# pic_blk.net
KiCad netlist of a schematic drawn in Altium Designer
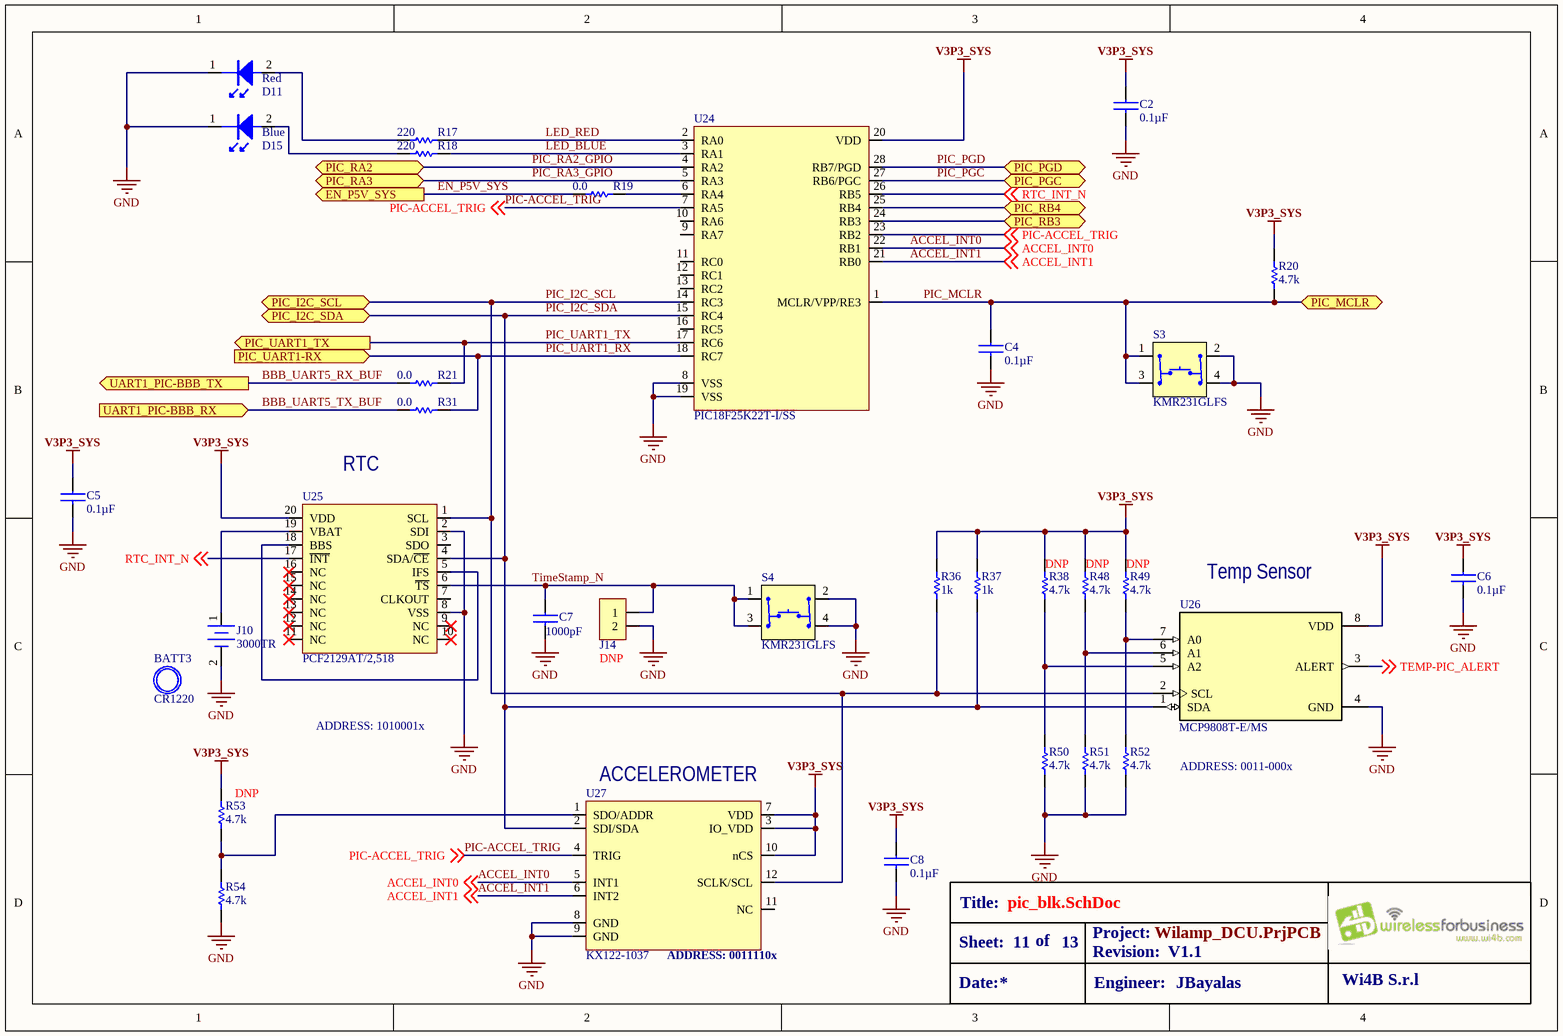
[diagram p0: pic_blk.SchDoc]

(export (version "E")
  (design (tool "Eeschema 10.0.6"))
  (components
    (comp (ref "BATT3")
      (value "CR1220")
      (description "Coin Cell Battery 35mAh 12.5mm")
      (fields (field (name "MPN") "CR1220"))
      (libsource (lib "Miscellaneous") (part "CR1220"))
    )
    (comp (ref "C2")
      (value "0.1µF")
      (footprint "C0402")
      (description "CAP CER 0.1UF 16V X7R 0402")
      (fields (field (name "MPN") "CL05B104KO3LNNC"))
      (libsource (lib "Capacitor") (part "CL05B104KO3LNNC"))
    )
    (comp (ref "C4")
      (value "0.1µF")
      (footprint "C0402")
      (description "CAP CER 0.1UF 16V X7R 0402")
      (fields (field (name "MPN") "CL05B104KO3LNNC"))
      (libsource (lib "Capacitor") (part "CL05B104KO3LNNC"))
    )
    (comp (ref "C5")
      (value "0.1µF")
      (footprint "C0402")
      (description "CAP CER 0.1UF 16V X7R 0402")
      (fields (field (name "MPN") "CL05B104KO3LNNC"))
      (libsource (lib "Capacitor") (part "CL05B104KO3LNNC"))
    )
    (comp (ref "C6")
      (value "0.1µF")
      (footprint "C0402")
      (description "CAP CER 0.1UF 16V X7R 0402")
      (fields (field (name "MPN") "CL05B104KO3LNNC"))
      (libsource (lib "Capacitor") (part "CL05B104KO3LNNC"))
    )
    (comp (ref "C7")
      (value "1000pF")
      (footprint "C0402")
      (description "CAP CER 1000PF 50V X7R 0402")
      (fields (field (name "MPN") "GRM155R71H102KA01D"))
      (libsource (lib "Capacitor") (part "GRM155R71H102KA01D"))
    )
    (comp (ref "C8")
      (value "0.1µF")
      (footprint "C0402")
      (description "CAP CER 0.1UF 16V X7R 0402")
      (fields (field (name "MPN") "CL05B104KO3LNNC"))
      (libsource (lib "Capacitor") (part "CL05B104KO3LNNC"))
    )
    (comp (ref "D11")
      (value "Red")
      (footprint "LED0402(RED)")
      (description "LED RED 0402 SMD")
      (fields (field (name "MPN") "LNJ247W82RA"))
      (libsource (lib "Diode") (part "LNJ247W82RA"))
    )
    (comp (ref "D15")
      (value "Blue")
      (footprint "LED0402(BLUE)")
      (description "LED BLUE 0402 SMD")
      (fields (field (name "MPN") "VLMB1500-GS08"))
      (libsource (lib "Diode") (part "VLMB1500-GS08"))
    )
    (comp (ref "J10")
      (value "3000TR")
      (footprint "3000TR")
      (description "Coin Cell Battery Holders SM COIN CELL B/H")
      (libsource (lib "Connector") (part "3000TR"))
    )
    (comp (ref "J14")
      (value "*")
      (footprint "2pin 5mm Pitch")
      (fields (field (name "LOAD") "DNP"))
      (libsource (lib "Miscellaneous") (part "2PIN Signal 5mm Pitch"))
    )
    (comp (ref "R17")
      (value "220")
      (footprint "R0402")
      (description "RES SMD 220 OHM 5% 1/16W 0402")
      (fields (field (name "MPN") "RC0402JR-07220RL"))
      (libsource (lib "Res") (part "RC0402JR-07220RL"))
    )
    (comp (ref "R18")
      (value "220")
      (footprint "R0402")
      (description "RES SMD 220 OHM 5% 1/16W 0402")
      (fields (field (name "MPN") "RC0402JR-07220RL"))
      (libsource (lib "Res") (part "RC0402JR-07220RL"))
    )
    (comp (ref "R19")
      (value "0.0")
      (footprint "R0402")
      (description "RES SMD 0.0OHM JUMPER 1/16W 0402")
      (fields (field (name "MPN") "CRCW04020000Z0ED"))
      (libsource (lib "Res") (part "CRCW04020000Z0ED"))
    )
    (comp (ref "R20")
      (value "4.7k")
      (footprint "R0603")
      (description "RES SMD 4.7K OHM 0.1% 1/10W 0603")
      (fields (field (name "MPN") "ERA-3AEB472V"))
      (libsource (lib "Res") (part "ERA-3AEB472V"))
    )
    (comp (ref "R21")
      (value "0.0")
      (footprint "R0402")
      (description "RES SMD 0.0OHM JUMPER 1/16W 0402")
      (fields (field (name "MPN") "CRCW04020000Z0ED"))
      (libsource (lib "Res") (part "CRCW04020000Z0ED"))
    )
    (comp (ref "R31")
      (value "0.0")
      (footprint "R0402")
      (description "RES SMD 0.0OHM JUMPER 1/16W 0402")
      (fields (field (name "MPN") "CRCW04020000Z0ED"))
      (libsource (lib "Res") (part "CRCW04020000Z0ED"))
    )
    (comp (ref "R36")
      (value "1k")
      (footprint "R0402")
      (description "RES SMD 1K OHM 1% 1/10W 0402")
      (fields (field (name "MPN") "MCS04020C1001FE000"))
      (libsource (lib "Res") (part "MCS04020C1001FE000"))
    )
    (comp (ref "R37")
      (value "1k")
      (footprint "R0402")
      (description "RES SMD 1K OHM 1% 1/10W 0402")
      (fields (field (name "MPN") "MCS04020C1001FE000"))
      (libsource (lib "Res") (part "MCS04020C1001FE000"))
    )
    (comp (ref "R38")
      (value "4.7k")
      (footprint "R0402")
      (description "RES SMD 4.7K OHM 5% 1/16W 0402")
      (fields (field (name "MPN") "RC0402JR-074K7L") (field (name "LOAD") "DNP"))
      (libsource (lib "Res") (part "RC0402JR-074K7L"))
    )
    (comp (ref "R48")
      (value "4.7k")
      (footprint "R0402")
      (description "RES SMD 4.7K OHM 5% 1/16W 0402")
      (fields (field (name "MPN") "RC0402JR-074K7L") (field (name "LOAD") "DNP"))
      (libsource (lib "Res") (part "RC0402JR-074K7L"))
    )
    (comp (ref "R49")
      (value "4.7k")
      (footprint "R0402")
      (description "RES SMD 4.7K OHM 5% 1/16W 0402")
      (fields (field (name "MPN") "RC0402JR-074K7L") (field (name "LOAD") "DNP"))
      (libsource (lib "Res") (part "RC0402JR-074K7L"))
    )
    (comp (ref "R50")
      (value "4.7k")
      (footprint "R0402")
      (description "RES SMD 4.7K OHM 5% 1/16W 0402")
      (fields (field (name "MPN") "RC0402JR-074K7L"))
      (libsource (lib "Res") (part "RC0402JR-074K7L"))
    )
    (comp (ref "R51")
      (value "4.7k")
      (footprint "R0402")
      (description "RES SMD 4.7K OHM 5% 1/16W 0402")
      (fields (field (name "MPN") "RC0402JR-074K7L"))
      (libsource (lib "Res") (part "RC0402JR-074K7L"))
    )
    (comp (ref "R52")
      (value "4.7k")
      (footprint "R0402")
      (description "RES SMD 4.7K OHM 5% 1/16W 0402")
      (fields (field (name "MPN") "RC0402JR-074K7L"))
      (libsource (lib "Res") (part "RC0402JR-074K7L"))
    )
    (comp (ref "R53")
      (value "4.7k")
      (footprint "R0402")
      (description "RES SMD 4.7K OHM 5% 1/16W 0402")
      (fields (field (name "MPN") "RC0402JR-074K7L") (field (name "LOAD") "DNP"))
      (libsource (lib "Res") (part "RC0402JR-074K7L"))
    )
    (comp (ref "R54")
      (value "4.7k")
      (footprint "R0402")
      (description "RES SMD 4.7K OHM 5% 1/16W 0402")
      (fields (field (name "MPN") "RC0402JR-074K7L"))
      (libsource (lib "Res") (part "RC0402JR-074K7L"))
    )
    (comp (ref "S3")
      (value "*")
      (footprint "KMR231G ULC LFS")
      (description "SWITCH TACTILE SPST-NO 0.05A 32V")
      (fields (field (name "MPN") "KMR231GLFS"))
      (libsource (lib "Switch") (part "KMR231GLFS"))
    )
    (comp (ref "S4")
      (value "*")
      (footprint "KMR231G ULC LFS")
      (description "SWITCH TACTILE SPST-NO 0.05A 32V")
      (fields (field (name "MPN") "KMR231GLFS"))
      (libsource (lib "Switch") (part "KMR231GLFS"))
    )
    (comp (ref "U24")
      (value "PIC18F25K22T-I/SS")
      (footprint "SSOP-28 (PIC)")
      (description "MCU 8BIT 32KB FLASH 28SSOP")
      (libsource (lib "IC") (part "PIC18F25K22T-I/SS"))
    )
    (comp (ref "U25")
      (value "PCF2129AT/2,518")
      (footprint "SOIC-20")
      (description "IC RTC /CALENDAR TCXO QTZ 20SOIC")
      (libsource (lib "IC") (part "PCF2129AT/2,518"))
    )
    (comp (ref "U26")
      (value "MCP9808T-E/MS")
      (footprint "SOP65P490X110-8N")
      (description "MCP9808 Series 3.6 V Memory Module Digital Temperature Sensor SMT - MSOP-8")
      (libsource (lib "SnapEDA") (part "MCP9808T-E/MS"))
    )
    (comp (ref "U27")
      (value "*")
      (footprint "KX122-1037")
      (description "ACCELEROMETER 2-8G I2C/SPI 12LGA")
      (fields (field (name "MPN") "KX122-1037"))
      (libsource (lib "IC") (part "KX122-1037"))
    )
  )
  (nets
    (net (code "1") (name "/BBB_UART5_RX_BUF") (class "Default")
      (node (ref "R21") (pin "2") (pinfunction "2_2") (pintype "passive"))
    )
    (net (code "2") (name "/BBB_UART5_TX_BUF") (class "Default")
      (node (ref "R31") (pin "2") (pinfunction "2_2") (pintype "passive"))
    )
    (net (code "3") (name "/EN_P5V_SYS") (class "Default")
      (node (ref "R19") (pin "2") (pinfunction "2_2") (pintype "passive"))
    )
    (net (code "4") (name "/LED_BLUE") (class "Default")
      (node (ref "R18") (pin "2") (pinfunction "2_2") (pintype "passive"))
      (node (ref "U24") (pin "3") (pinfunction "RA1_3") (pintype "passive"))
    )
    (net (code "5") (name "/LED_RED") (class "Default")
      (node (ref "R17") (pin "2") (pinfunction "2_2") (pintype "passive"))
      (node (ref "U24") (pin "2") (pinfunction "RA0_2") (pintype "passive"))
    )
    (net (code "6") (name "/PIC_I2C_SCL") (class "Default")
      (node (ref "R36") (pin "1") (pinfunction "1_1") (pintype "passive"))
      (node (ref "U24") (pin "14") (pinfunction "RC3_14") (pintype "passive"))
      (node (ref "U25") (pin "1") (pinfunction "SCL_1") (pintype "passive"))
      (node (ref "U26") (pin "2") (pinfunction "SCL_2") (pintype "input"))
      (node (ref "U27") (pin "12") (pinfunction "SCLK/SCL_12") (pintype "passive"))
    )
    (net (code "7") (name "/PIC_I2C_SDA") (class "Default")
      (node (ref "R37") (pin "1") (pinfunction "1_1") (pintype "passive"))
      (node (ref "U24") (pin "15") (pinfunction "RC4_15") (pintype "passive"))
      (node (ref "U25") (pin "4") (pinfunction "SDA/~{CE}_4") (pintype "passive"))
      (node (ref "U26") (pin "1") (pinfunction "SDA_1") (pintype "bidirectional"))
      (node (ref "U27") (pin "2") (pinfunction "SDI/SDA_2") (pintype "passive"))
    )
    (net (code "8") (name "/PIC_MCLR") (class "Default")
      (node (ref "C4") (pin "1") (pinfunction "1_1") (pintype "passive"))
      (node (ref "R20") (pin "1") (pinfunction "1_1") (pintype "passive"))
      (node (ref "S3") (pin "1") (pinfunction "1_1") (pintype "passive"))
      (node (ref "S3") (pin "3") (pinfunction "3_3") (pintype "passive"))
      (node (ref "U24") (pin "1") (pinfunction "MCLR/VPP/RE3_1") (pintype "passive"))
    )
    (net (code "9") (name "/PIC_PGC") (class "Default")
      (node (ref "U24") (pin "27") (pinfunction "RB6/PGC_27") (pintype "passive"))
    )
    (net (code "10") (name "/PIC_PGD") (class "Default")
      (node (ref "U24") (pin "28") (pinfunction "RB7/PGD_28") (pintype "passive"))
    )
    (net (code "11") (name "/PIC_RA2_GPIO") (class "Default")
      (node (ref "U24") (pin "4") (pinfunction "RA2_4") (pintype "passive"))
    )
    (net (code "12") (name "/PIC_RA3_GPIO") (class "Default")
      (node (ref "U24") (pin "5") (pinfunction "RA3_5") (pintype "passive"))
    )
    (net (code "13") (name "/PIC_RB3") (class "Default")
      (node (ref "U24") (pin "24") (pinfunction "RB3_24") (pintype "passive"))
    )
    (net (code "14") (name "/PIC_RB4") (class "Default")
      (node (ref "U24") (pin "25") (pinfunction "RB4_25") (pintype "passive"))
    )
    (net (code "15") (name "/PIC_UART1_RX") (class "Default")
      (node (ref "R31") (pin "1") (pinfunction "1_1") (pintype "passive"))
      (node (ref "U24") (pin "18") (pinfunction "RC7_18") (pintype "passive"))
    )
    (net (code "16") (name "/PIC_UART1_TX") (class "Default")
      (node (ref "R21") (pin "1") (pinfunction "1_1") (pintype "passive"))
      (node (ref "U24") (pin "17") (pinfunction "RC6_17") (pintype "passive"))
    )
    (net (code "17") (name "/TimeStamp_N") (class "Default")
      (node (ref "C7") (pin "1") (pinfunction "1_1") (pintype "passive"))
      (node (ref "J14") (pin "1") (pinfunction "1_1") (pintype "passive"))
      (node (ref "S4") (pin "1") (pinfunction "1_1") (pintype "passive"))
      (node (ref "S4") (pin "3") (pinfunction "3_3") (pintype "passive"))
      (node (ref "U25") (pin "6") (pinfunction "~{TS}_6") (pintype "passive"))
    )
    (net (code "18") (name "ACCEL_INT0") (class "Default")
      (node (ref "U24") (pin "22") (pinfunction "RB1_22") (pintype "passive"))
      (node (ref "U27") (pin "5") (pinfunction "INT1_5") (pintype "passive"))
    )
    (net (code "19") (name "ACCEL_INT1") (class "Default")
      (node (ref "U24") (pin "21") (pinfunction "RB0_21") (pintype "passive"))
      (node (ref "U27") (pin "6") (pinfunction "INT2_6") (pintype "passive"))
    )
    (net (code "20") (name "GND") (class "Default")
      (node (ref "C2") (pin "2") (pinfunction "2_2") (pintype "passive"))
      (node (ref "C4") (pin "2") (pinfunction "2_2") (pintype "passive"))
      (node (ref "C5") (pin "2") (pinfunction "2_2") (pintype "passive"))
      (node (ref "C6") (pin "2") (pinfunction "2_2") (pintype "passive"))
      (node (ref "C7") (pin "2") (pinfunction "2_2") (pintype "passive"))
      (node (ref "C8") (pin "2") (pinfunction "2_2") (pintype "passive"))
      (node (ref "D11") (pin "1") (pinfunction "1_1") (pintype "passive"))
      (node (ref "D15") (pin "1") (pinfunction "1_1") (pintype "passive"))
      (node (ref "J10") (pin "2") (pinfunction "-_2") (pintype "passive"))
      (node (ref "J14") (pin "2") (pinfunction "2_2") (pintype "passive"))
      (node (ref "R50") (pin "1") (pinfunction "1_1") (pintype "passive"))
      (node (ref "R51") (pin "1") (pinfunction "1_1") (pintype "passive"))
      (node (ref "R52") (pin "1") (pinfunction "1_1") (pintype "passive"))
      (node (ref "R54") (pin "1") (pinfunction "1_1") (pintype "passive"))
      (node (ref "S3") (pin "2") (pinfunction "2_2") (pintype "passive"))
      (node (ref "S3") (pin "4") (pinfunction "4_4") (pintype "passive"))
      (node (ref "S4") (pin "2") (pinfunction "2_2") (pintype "passive"))
      (node (ref "S4") (pin "4") (pinfunction "4_4") (pintype "passive"))
      (node (ref "U24") (pin "19") (pinfunction "VSS_19") (pintype "passive"))
      (node (ref "U24") (pin "8") (pinfunction "VSS_8") (pintype "passive"))
      (node (ref "U25") (pin "2") (pinfunction "SDI_2") (pintype "passive"))
      (node (ref "U25") (pin "8") (pinfunction "VSS_8") (pintype "passive"))
      (node (ref "U26") (pin "4") (pinfunction "GND_4") (pintype "power_in"))
      (node (ref "U27") (pin "8") (pinfunction "GND_8") (pintype "passive"))
      (node (ref "U27") (pin "9") (pinfunction "GND_9") (pintype "passive"))
    )
    (net (code "21") (name "Net-(D11-Pad2)") (class "Default")
      (node (ref "D11") (pin "2") (pinfunction "2_2") (pintype "passive"))
      (node (ref "R17") (pin "1") (pinfunction "1_1") (pintype "passive"))
    )
    (net (code "22") (name "Net-(D15-Pad2)") (class "Default")
      (node (ref "D15") (pin "2") (pinfunction "2_2") (pintype "passive"))
      (node (ref "R18") (pin "1") (pinfunction "1_1") (pintype "passive"))
    )
    (net (code "23") (name "Net-(J10-+)") (class "Default")
      (node (ref "J10") (pin "1") (pinfunction "+_1") (pintype "passive"))
      (node (ref "U25") (pin "19") (pinfunction "VBAT_19") (pintype "passive"))
    )
    (net (code "24") (name "Net-(U24-RA4)") (class "Default")
      (node (ref "R19") (pin "1") (pinfunction "1_1") (pintype "passive"))
      (node (ref "U24") (pin "6") (pinfunction "RA4_6") (pintype "passive"))
    )
    (net (code "25") (name "Net-(U25-BBS)") (class "Default")
      (node (ref "U25") (pin "18") (pinfunction "BBS_18") (pintype "passive"))
      (node (ref "U25") (pin "5") (pinfunction "IFS_5") (pintype "passive"))
    )
    (net (code "26") (name "Net-(U26-A0)") (class "Default")
      (node (ref "R49") (pin "1") (pinfunction "1_1") (pintype "passive"))
      (node (ref "R52") (pin "2") (pinfunction "2_2") (pintype "passive"))
      (node (ref "U26") (pin "7") (pinfunction "A0_7") (pintype "input"))
    )
    (net (code "27") (name "Net-(U26-A1)") (class "Default")
      (node (ref "R48") (pin "1") (pinfunction "1_1") (pintype "passive"))
      (node (ref "R51") (pin "2") (pinfunction "2_2") (pintype "passive"))
      (node (ref "U26") (pin "6") (pinfunction "A1_6") (pintype "input"))
    )
    (net (code "28") (name "Net-(U26-A2)") (class "Default")
      (node (ref "R38") (pin "1") (pinfunction "1_1") (pintype "passive"))
      (node (ref "R50") (pin "2") (pinfunction "2_2") (pintype "passive"))
      (node (ref "U26") (pin "5") (pinfunction "A2_5") (pintype "input"))
    )
    (net (code "29") (name "Net-(U27-SDO{slash}ADDR)") (class "Default")
      (node (ref "R53") (pin "1") (pinfunction "1_1") (pintype "passive"))
      (node (ref "R54") (pin "2") (pinfunction "2_2") (pintype "passive"))
      (node (ref "U27") (pin "1") (pinfunction "SDO/ADDR_1") (pintype "passive"))
    )
    (net (code "30") (name "PIC-ACCEL_TRIG") (class "Default")
      (node (ref "U24") (pin "23") (pinfunction "RB2_23") (pintype "passive"))
      (node (ref "U24") (pin "7") (pinfunction "RA5_7") (pintype "passive"))
      (node (ref "U27") (pin "4") (pinfunction "TRIG_4") (pintype "passive"))
    )
    (net (code "31") (name "RTC_INT_N") (class "Default")
      (node (ref "U24") (pin "26") (pinfunction "RB5_26") (pintype "passive"))
      (node (ref "U25") (pin "17") (pinfunction "~{INT}_17") (pintype "passive"))
    )
    (net (code "32") (name "TEMP-PIC_ALERT") (class "Default")
      (node (ref "U26") (pin "3") (pinfunction "ALERT_3") (pintype "output"))
    )
    (net (code "33") (name "V3P3_SYS") (class "Default")
      (node (ref "C2") (pin "1") (pinfunction "1_1") (pintype "passive"))
      (node (ref "C5") (pin "1") (pinfunction "1_1") (pintype "passive"))
      (node (ref "C6") (pin "1") (pinfunction "1_1") (pintype "passive"))
      (node (ref "C8") (pin "1") (pinfunction "1_1") (pintype "passive"))
      (node (ref "R20") (pin "2") (pinfunction "2_2") (pintype "passive"))
      (node (ref "R36") (pin "2") (pinfunction "2_2") (pintype "passive"))
      (node (ref "R37") (pin "2") (pinfunction "2_2") (pintype "passive"))
      (node (ref "R38") (pin "2") (pinfunction "2_2") (pintype "passive"))
      (node (ref "R48") (pin "2") (pinfunction "2_2") (pintype "passive"))
      (node (ref "R49") (pin "2") (pinfunction "2_2") (pintype "passive"))
      (node (ref "R53") (pin "2") (pinfunction "2_2") (pintype "passive"))
      (node (ref "U24") (pin "20") (pinfunction "VDD_20") (pintype "passive"))
      (node (ref "U25") (pin "20") (pinfunction "VDD_20") (pintype "passive"))
      (node (ref "U26") (pin "8") (pinfunction "VDD_8") (pintype "power_in"))
      (node (ref "U27") (pin "10") (pinfunction "nCS_10") (pintype "passive"))
      (node (ref "U27") (pin "3") (pinfunction "IO_VDD_3") (pintype "passive"))
      (node (ref "U27") (pin "7") (pinfunction "VDD_7") (pintype "passive"))
    )
    (net (code "34") (name "unconnected-(U24-RA6-Pad10)") (class "Default")
      (node (ref "U24") (pin "10") (pinfunction "RA6_10") (pintype "passive"))
    )
    (net (code "35") (name "unconnected-(U24-RA7-Pad9)") (class "Default")
      (node (ref "U24") (pin "9") (pinfunction "RA7_9") (pintype "passive"))
    )
    (net (code "36") (name "unconnected-(U24-RC0-Pad11)") (class "Default")
      (node (ref "U24") (pin "11") (pinfunction "RC0_11") (pintype "passive"))
    )
    (net (code "37") (name "unconnected-(U24-RC1-Pad12)") (class "Default")
      (node (ref "U24") (pin "12") (pinfunction "RC1_12") (pintype "passive"))
    )
    (net (code "38") (name "unconnected-(U24-RC2-Pad13)") (class "Default")
      (node (ref "U24") (pin "13") (pinfunction "RC2_13") (pintype "passive"))
    )
    (net (code "39") (name "unconnected-(U24-RC5-Pad16)") (class "Default")
      (node (ref "U24") (pin "16") (pinfunction "RC5_16") (pintype "passive"))
    )
    (net (code "40") (name "unconnected-(U25-CLKOUT-Pad7)") (class "Default")
      (node (ref "U25") (pin "7") (pinfunction "CLKOUT_7") (pintype "passive"))
    )
    (net (code "41") (name "unconnected-(U25-NC-Pad9)") (class "Default")
      (node (ref "U25") (pin "9") (pinfunction "NC_9") (pintype "passive+no_connect"))
    )
    (net (code "42") (name "unconnected-(U25-NC-Pad10)") (class "Default")
      (node (ref "U25") (pin "10") (pinfunction "NC_10") (pintype "passive+no_connect"))
    )
    (net (code "43") (name "unconnected-(U25-NC-Pad11)") (class "Default")
      (node (ref "U25") (pin "11") (pinfunction "NC_11") (pintype "passive+no_connect"))
    )
    (net (code "44") (name "unconnected-(U25-NC-Pad12)") (class "Default")
      (node (ref "U25") (pin "12") (pinfunction "NC_12") (pintype "passive+no_connect"))
    )
    (net (code "45") (name "unconnected-(U25-NC-Pad13)") (class "Default")
      (node (ref "U25") (pin "13") (pinfunction "NC_13") (pintype "passive+no_connect"))
    )
    (net (code "46") (name "unconnected-(U25-NC-Pad14)") (class "Default")
      (node (ref "U25") (pin "14") (pinfunction "NC_14") (pintype "passive+no_connect"))
    )
    (net (code "47") (name "unconnected-(U25-NC-Pad15)") (class "Default")
      (node (ref "U25") (pin "15") (pinfunction "NC_15") (pintype "passive+no_connect"))
    )
    (net (code "48") (name "unconnected-(U25-NC-Pad16)") (class "Default")
      (node (ref "U25") (pin "16") (pinfunction "NC_16") (pintype "passive+no_connect"))
    )
    (net (code "49") (name "unconnected-(U25-SDO-Pad3)") (class "Default")
      (node (ref "U25") (pin "3") (pinfunction "SDO_3") (pintype "passive"))
    )
    (net (code "50") (name "unconnected-(U27-NC-Pad11)") (class "Default")
      (node (ref "U27") (pin "11") (pinfunction "NC_11") (pintype "passive"))
    )
  )
)
